# LighterBoard.net
KiCad netlist of a schematic drawn in EAGLE
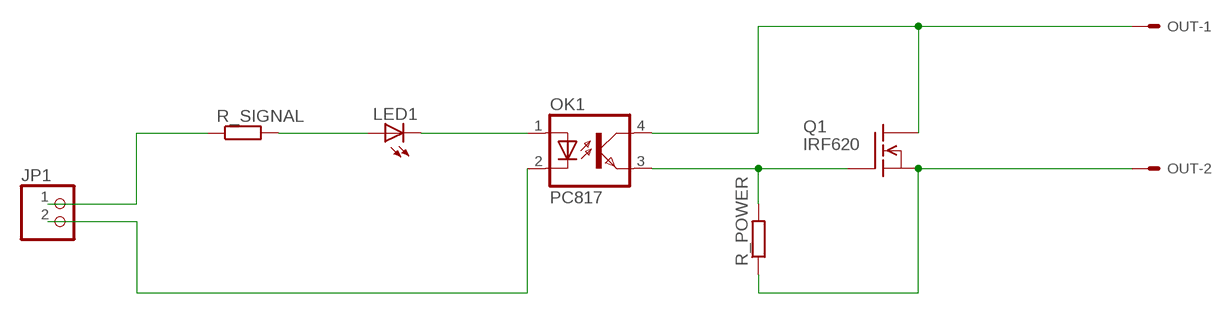
[diagram p0: schematic, sheet 1]

(export (version "E")
  (design (tool "Eeschema 10.0.6"))
  (components
    (comp (ref "JP1")
      (value "PINHD-1X2")
      (footprint "eagle-import:1X02")
      (libsource (lib "eagle-import") (part "PINHD-1X2"))
    )
    (comp (ref "LED1")
      (value "LED5MM")
      (footprint "eagle-import:LED5MM")
      (libsource (lib "eagle-import") (part "LED5MM"))
    )
    (comp (ref "OK1")
      (value "PC817")
      (footprint "eagle-import:DIL04")
      (fields (field (name "MPN") "PC817X4J000F"))
      (libsource (lib "eagle-import") (part "PC817"))
    )
    (comp (ref "OUT")
      (value "KK-156-2")
      (footprint "eagle-import:KK-156-2")
      (libsource (lib "eagle-import") (part "KK-156-2"))
    )
    (comp (ref "Q1")
      (value "IRF620")
      (footprint "eagle-import:TO220V")
      (libsource (lib "eagle-import") (part "IRF620"))
    )
    (comp (ref "R_POWER")
      (value "R-EU_0207/10")
      (footprint "eagle-import:0207_10")
      (libsource (lib "eagle-import") (part "R-EU_0207/10"))
    )
    (comp (ref "R_SIGNAL")
      (value "R-EU_0207/10")
      (footprint "eagle-import:0207_10")
      (libsource (lib "eagle-import") (part "R-EU_0207/10"))
    )
  )
  (nets
    (net (code "1") (name "Net-(JP1-Pad1)") (class "Default")
      (node (ref "JP1") (pin "1") (pinfunction "1_1") (pintype "passive"))
      (node (ref "R_SIGNAL") (pin "1") (pinfunction "1_1") (pintype "passive"))
    )
    (net (code "2") (name "Net-(LED1-C)") (class "Default")
      (node (ref "LED1") (pin "K") (pinfunction "C_K") (pintype "passive"))
      (node (ref "OK1") (pin "1") (pinfunction "A_1") (pintype "passive"))
    )
    (net (code "3") (name "Net-(LED1-PadA)") (class "Default")
      (node (ref "LED1") (pin "A") (pinfunction "A_A") (pintype "passive"))
      (node (ref "R_SIGNAL") (pin "2") (pinfunction "2_2") (pintype "passive"))
    )
    (net (code "4") (name "Net-(OK1-C)") (class "Default")
      (node (ref "JP1") (pin "2") (pinfunction "2_2") (pintype "passive"))
      (node (ref "OK1") (pin "2") (pinfunction "C_2") (pintype "passive"))
    )
    (net (code "5") (name "Net-(OK1-COL)") (class "Default")
      (node (ref "OK1") (pin "4") (pinfunction "COL_4") (pintype "passive"))
      (node (ref "OUT") (pin "1") (pinfunction "S_1") (pintype "passive"))
      (node (ref "Q1") (pin "2") (pinfunction "D_2") (pintype "passive"))
    )
    (net (code "6") (name "Net-(OK1-EMIT)") (class "Default")
      (node (ref "OK1") (pin "3") (pinfunction "EMIT_3") (pintype "passive"))
      (node (ref "Q1") (pin "1") (pinfunction "G_1") (pintype "passive"))
      (node (ref "R_POWER") (pin "2") (pinfunction "2_2") (pintype "passive"))
    )
    (net (code "7") (name "Net-(OUTB-S)") (class "Default")
      (node (ref "OUT") (pin "2") (pinfunction "S_2") (pintype "passive"))
      (node (ref "Q1") (pin "3") (pinfunction "S_3") (pintype "passive"))
      (node (ref "R_POWER") (pin "1") (pinfunction "1_1") (pintype "passive"))
    )
  )
)
